# Battery_Guage.net
KiCad netlist of a schematic drawn in Altium Designer
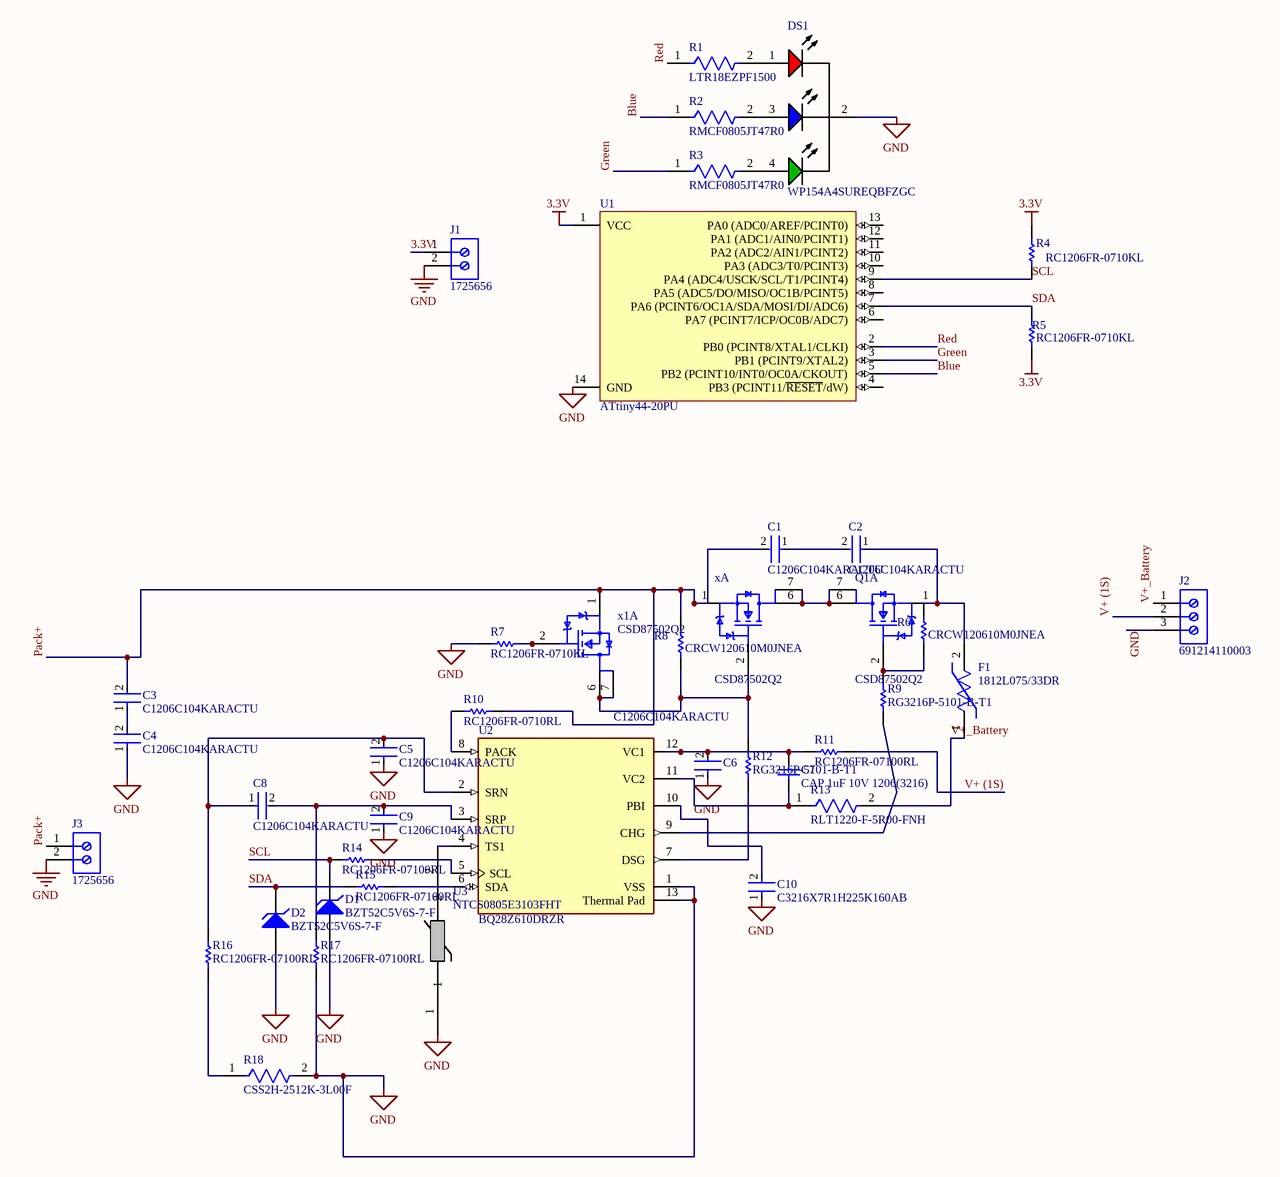
[diagram p0: Battery_Guage.SchDoc]

(export (version "E")
  (design (tool "Eeschema 10.0.6"))
  (components
    (comp (ref "C1")
      (value "C1206C104KARACTU")
      (footprint "FP-C1206C-EB-MFG")
      (description "CAP CER 0.1UF 250V X7R 1206")
      (fields (field (name "MANUFACTURER") "KEMET") (field (name "TOLERANCE") "0.1"))
      (libsource (lib "Altium Content Vault") (part "b4654b650e69147ec39a6b967a45e02"))
    )
    (comp (ref "C2")
      (value "C1206C104KARACTU")
      (footprint "FP-C1206C-EB-MFG")
      (description "CAP CER 0.1UF 250V X7R 1206")
      (fields (field (name "MANUFACTURER") "KEMET") (field (name "TOLERANCE") "0.1"))
      (libsource (lib "Altium Content Vault") (part "b4654b650e69147ec39a6b967a45e02"))
    )
    (comp (ref "C3")
      (value "C1206C104KARACTU")
      (footprint "FP-C1206C-EB-MFG")
      (description "CAP CER 0.1UF 250V X7R 1206")
      (fields (field (name "MANUFACTURER") "KEMET") (field (name "TOLERANCE") "0.1"))
      (libsource (lib "Altium Content Vault") (part "b4654b650e69147ec39a6b967a45e02"))
    )
    (comp (ref "C4")
      (value "C1206C104KARACTU")
      (footprint "FP-C1206C-EB-MFG")
      (description "CAP CER 0.1UF 250V X7R 1206")
      (fields (field (name "MANUFACTURER") "KEMET") (field (name "TOLERANCE") "0.1"))
      (libsource (lib "Altium Content Vault") (part "b4654b650e69147ec39a6b967a45e02"))
    )
    (comp (ref "C5")
      (value "C1206C104KARACTU")
      (footprint "FP-C1206C-EB-MFG")
      (description "CAP CER 0.1UF 250V X7R 1206")
      (fields (field (name "MANUFACTURER") "KEMET") (field (name "TOLERANCE") "0.1"))
      (libsource (lib "Altium Content Vault") (part "b4654b650e69147ec39a6b967a45e02"))
    )
    (comp (ref "C6")
      (value "C1206C104KARACTU")
      (footprint "FP-C1206C-EB-MFG")
      (description "CAP CER 0.1UF 250V X7R 1206")
      (fields (field (name "MANUFACTURER") "KEMET") (field (name "TOLERANCE") "0.1"))
      (libsource (lib "Altium Content Vault") (part "b4654b650e69147ec39a6b967a45e02"))
    )
    (comp (ref "C7")
      (value "CAP 1uF 10V 1206(3216)")
      (footprint "CAPC1206(3216)130_L")
      (description "CAP 1uF 10V ±20% 1206 (3216 Metric) Thickness 1.3mm SMD")
      (fields (field (name "TOLERANCE") "Â±20%"))
      (libsource (lib "Altium Content Vault") (part "CAP"))
    )
    (comp (ref "C8")
      (value "C1206C104KARACTU")
      (footprint "FP-C1206C-EB-MFG")
      (description "CAP CER 0.1UF 250V X7R 1206")
      (fields (field (name "MANUFACTURER") "KEMET") (field (name "TOLERANCE") "0.1"))
      (libsource (lib "Altium Content Vault") (part "b4654b650e69147ec39a6b967a45e02"))
    )
    (comp (ref "C9")
      (value "C1206C104KARACTU")
      (footprint "FP-C1206C-EB-MFG")
      (description "CAP CER 0.1UF 250V X7R 1206")
      (fields (field (name "MANUFACTURER") "KEMET") (field (name "TOLERANCE") "0.1"))
      (libsource (lib "Altium Content Vault") (part "b4654b650e69147ec39a6b967a45e02"))
    )
    (comp (ref "C10")
      (value "C3216X7R1H225K160AB")
      (footprint "FP-C3216-160-0_2-IPC_A")
      (description "Multilayer Ceramic Capacitors 2.2uF ±10% 50V X7R SMD 1206")
      (fields (field (name "TOLERANCE") "10%"))
      (libsource (lib "Altium Content Vault") (part "11868f565c42a9108669ba33697ecf6"))
    )
    (comp (ref "D1")
      (value "BZT52C5V6S-7-F")
      (footprint "DIOD-SOD323-2_V")
      (description "Surface Mount Zener Diode, 5.6 V, -65 to 150 degC, 2-Pin SOD323, RoHS, Tape and Reel")
      (fields (field (name "MANUFACTURER") "DiodesIncorporated"))
      (libsource (lib "Altium Content Vault") (part "DZEN-AK-2"))
    )
    (comp (ref "D2")
      (value "BZT52C5V6S-7-F")
      (footprint "DIOD-SOD323-2_V")
      (description "Surface Mount Zener Diode, 5.6 V, -65 to 150 degC, 2-Pin SOD323, RoHS, Tape and Reel")
      (fields (field (name "MANUFACTURER") "DiodesIncorporated"))
      (libsource (lib "Altium Content Vault") (part "DZEN-AK-2"))
    )
    (comp (ref "DS1")
      (value "WP154A4SUREQBFZGC")
      (footprint "KING-WP154A4SUREQBFZGC_V")
      (description "Full Color LED Lamp, Dominant Wavelength RGB 630 / 525 / 465 nm, -40 to 85 degC, 4-Pin THD, RoHS")
      (fields (field (name "MANUFACTURER") "Kingbright"))
      (libsource (lib "Altium Content Vault") (part "LED-RGB-AKAA-4"))
    )
    (comp (ref "F1")
      (value "1812L075/33DR")
      (footprint "FP-1812L075-33DR-MFG")
      (description "PTC RESET FUSE 33V 750MA 1812")
      (libsource (lib "Altium Content Vault") (part "fdf083d5f6389a9a1c4e51137f46658"))
    )
    (comp (ref "J1")
      (value "1725656")
      (footprint "PHOE-1725656-2")
      (description "Male Header, Pitch 2.54 mm, 1 x 2 Position, Height 9 mm, Tail Length 3.5 mm")
      (fields (field (name "MANUFACTURER") "Phoenix Contact"))
      (libsource (lib "Altium Content Vault") (part "CN-1P-F-TB2"))
    )
    (comp (ref "J2")
      (value "691214110003")
      (footprint "691214110003")
      (fields (field (name "VOLTAGE") "300V"))
      (libsource (lib "Altium Content Vault") (part "TBL - 1R - 03P - Screw"))
    )
    (comp (ref "J3")
      (value "1725656")
      (footprint "PHOE-1725656-2")
      (description "Male Header, Pitch 2.54 mm, 1 x 2 Position, Height 9 mm, Tail Length 3.5 mm")
      (fields (field (name "MANUFACTURER") "Phoenix Contact"))
      (libsource (lib "Altium Content Vault") (part "CN-1P-F-TB2"))
    )
    (comp (ref "Q1")
      (value "CSD87502Q2")
      (footprint "FP-DQK0006B-MFG")
      (description "MOSFET 2N-CH 30V 5A 6WSON")
      (libsource (lib "Altium Content Vault") (part "fd3cbd9991b3bb74591be4f9c2484a9"))
    )
    (comp (ref "R1")
      (value "LTR18EZPF1500")
      (footprint "FP-LTR18-IPC_A")
      (description "High power chip resistors wide terminal type 150Ω 1% 0.75W 0612")
      (fields (field (name "TOLERANCE") "1%"))
      (libsource (lib "Altium Content Vault") (part "1029c3af85768c4190bb7ad29bc67b5"))
    )
    (comp (ref "R2")
      (value "RMCF0805JT47R0")
      (footprint "FP-RMCF0805-MFG")
      (description "47Ω ±5% 0.125W 0805 Thick Film Chip Resistor AEC-Q200 compliant")
      (fields (field (name "TOLERANCE") "5%"))
      (libsource (lib "Altium Content Vault") (part "1029c3af85768c4190bb7ad29bc67b5"))
    )
    (comp (ref "R3")
      (value "RMCF0805JT47R0")
      (footprint "FP-RMCF0805-MFG")
      (description "47Ω ±5% 0.125W 0805 Thick Film Chip Resistor AEC-Q200 compliant")
      (fields (field (name "TOLERANCE") "5%"))
      (libsource (lib "Altium Content Vault") (part "1029c3af85768c4190bb7ad29bc67b5"))
    )
    (comp (ref "R4")
      (value "RC1206FR-0710KL")
      (footprint "RESC3116X65X40ML10T20")
      (description "Chip Resistor, 10 KOhm, +/- 1%, 0.25 W, -55 to 155 degC, 1206 (3216 Metric), RoHS, Tape and Reel")
      (fields (field (name "TOLERANCE") "1%") (field (name "MANUFACTURER") "Yageo"))
      (libsource (lib "Altium Content Vault") (part "RES-2"))
    )
    (comp (ref "R5")
      (value "RC1206FR-0710KL")
      (footprint "RESC3116X65X40ML10T20")
      (description "Chip Resistor, 10 KOhm, +/- 1%, 0.25 W, -55 to 155 degC, 1206 (3216 Metric), RoHS, Tape and Reel")
      (fields (field (name "TOLERANCE") "1%") (field (name "MANUFACTURER") "Yageo"))
      (libsource (lib "Altium Content Vault") (part "RES-2"))
    )
    (comp (ref "R6")
      (value "CRCW120610M0JNEA")
      (footprint "RESC3216X60X45LL10T20")
      (fields (field (name "MANUFACTURER") "Vishay Dale"))
      (libsource (lib "Altium Content Vault") (part "RES"))
    )
    (comp (ref "R7")
      (value "RC1206FR-0710KL")
      (footprint "RESC3116X65X40ML10T20")
      (description "Chip Resistor, 10 KOhm, +/- 1%, 0.25 W, -55 to 155 degC, 1206 (3216 Metric), RoHS, Tape and Reel")
      (fields (field (name "TOLERANCE") "1%") (field (name "MANUFACTURER") "Yageo"))
      (libsource (lib "Altium Content Vault") (part "RES-2"))
    )
    (comp (ref "R8")
      (value "CRCW120610M0JNEA")
      (footprint "RESC3216X60X45LL10T20")
      (fields (field (name "MANUFACTURER") "Vishay Dale"))
      (libsource (lib "Altium Content Vault") (part "RES"))
    )
    (comp (ref "R9")
      (value "RG3216P-5101-B-T1")
      (footprint "RESC3216X50X50NL20T25")
      (fields (field (name "MANUFACTURER") "Susumu"))
      (libsource (lib "Altium Content Vault") (part "RES"))
    )
    (comp (ref "R10")
      (value "RC1206FR-0710RL")
      (footprint "RESC3116X65X40ML10T20")
      (description "Chip Resistor, 10 Ohm, +/- 1%, 0.25 W, -55 to 155 degC, 1206 (3216 Metric), RoHS, Tape and Reel")
      (fields (field (name "MANUFACTURER") "Yageo") (field (name "TOLERANCE") "1%"))
      (libsource (lib "Altium Content Vault") (part "RES-2"))
    )
    (comp (ref "R11")
      (value "RC1206FR-07100RL")
      (footprint "RESC3116X65X40ML10T20")
      (description "Chip Resistor, 100 Ohm, +/- 1%, 0.25 W, -55 to 155 degC, 1206 (3216 Metric), RoHS, Tape and Reel")
      (fields (field (name "MANUFACTURER") "Yageo") (field (name "TOLERANCE") "1%"))
      (libsource (lib "Altium Content Vault") (part "RES-2"))
    )
    (comp (ref "R12")
      (value "RG3216P-5101-B-T1")
      (footprint "RESC3216X50X50NL20T25")
      (fields (field (name "MANUFACTURER") "Susumu"))
      (libsource (lib "Altium Content Vault") (part "RES"))
    )
    (comp (ref "R13")
      (value "RLT1220-F-5R00-FNH")
      (footprint "FP-RLT1220-F-MFG")
      (description "RES SMD 5 OHM 1% 1/3W 0805")
      (libsource (lib "Altium Content Vault") (part "1029c3af85768c4190bb7ad29bc67b5"))
    )
    (comp (ref "R14")
      (value "RC1206FR-07100RL")
      (footprint "RESC3116X65X40ML10T20")
      (description "Chip Resistor, 100 Ohm, +/- 1%, 0.25 W, -55 to 155 degC, 1206 (3216 Metric), RoHS, Tape and Reel")
      (fields (field (name "MANUFACTURER") "Yageo") (field (name "TOLERANCE") "1%"))
      (libsource (lib "Altium Content Vault") (part "RES-2"))
    )
    (comp (ref "R15")
      (value "RC1206FR-07100RL")
      (footprint "RESC3116X65X40ML10T20")
      (description "Chip Resistor, 100 Ohm, +/- 1%, 0.25 W, -55 to 155 degC, 1206 (3216 Metric), RoHS, Tape and Reel")
      (fields (field (name "MANUFACTURER") "Yageo") (field (name "TOLERANCE") "1%"))
      (libsource (lib "Altium Content Vault") (part "RES-2"))
    )
    (comp (ref "R16")
      (value "RC1206FR-07100RL")
      (footprint "RESC3116X65X40ML10T20")
      (description "Chip Resistor, 100 Ohm, +/- 1%, 0.25 W, -55 to 155 degC, 1206 (3216 Metric), RoHS, Tape and Reel")
      (fields (field (name "MANUFACTURER") "Yageo") (field (name "TOLERANCE") "1%"))
      (libsource (lib "Altium Content Vault") (part "RES-2"))
    )
    (comp (ref "R17")
      (value "RC1206FR-07100RL")
      (footprint "RESC3116X65X40ML10T20")
      (description "Chip Resistor, 100 Ohm, +/- 1%, 0.25 W, -55 to 155 degC, 1206 (3216 Metric), RoHS, Tape and Reel")
      (fields (field (name "MANUFACTURER") "Yageo") (field (name "TOLERANCE") "1%"))
      (libsource (lib "Altium Content Vault") (part "RES-2"))
    )
    (comp (ref "R18")
      (value "CSS2H-2512K-3L00F")
      (footprint "FP-CSS2H-2512K-3L00F-MFG")
      (description "CSS2H-2512K-3L00F Res Metal Strip 2512 0.003 Ohm 1% 4W ±75ppm/C Pad SMD Automotive T/R")
      (fields (field (name "TOLERANCE") "1%"))
      (libsource (lib "Altium Content Vault") (part "1029c3af85768c4190bb7ad29bc67b5"))
    )
    (comp (ref "U1")
      (value "ATtiny44-20PU")
      (footprint "14P3")
      (libsource (lib "Altium Content Vault") (part "MC-8B-ATTINY24V-IL14"))
    )
    (comp (ref "U2")
      (value "BQ28Z610DRZR")
      (footprint "FP-DRZ0012A-MFG")
      (description "IC BATT GAS GAUGE LIION 12SON")
      (libsource (lib "Altium Content Vault") (part "45a40ba0b7cf2a0dd5636c134825ee4"))
    )
    (comp (ref "U3")
      (value "NTCS0805E3103FHT")
      (footprint "NTCS0805_VIS")
      (description "THERMISTOR NTC 10KOHM 3940K 0805")
      (fields (field (name "TOLERANCE") "1%"))
      (libsource (lib "Altium Content Vault") (part "NTCS0805E3103FHT"))
    )
    (comp (ref "x")
      (value "CSD87502Q2")
      (footprint "FP-DQK0006B-MFG")
      (description "MOSFET 2N-CH 30V 5A 6WSON")
      (libsource (lib "Altium Content Vault") (part "fd3cbd9991b3bb74591be4f9c2484a9"))
    )
    (comp (ref "x1")
      (value "CSD87502Q2")
      (footprint "FP-DQK0006B-MFG")
      (description "MOSFET 2N-CH 30V 5A 6WSON")
      (libsource (lib "Altium Content Vault") (part "fd3cbd9991b3bb74591be4f9c2484a9"))
    )
  )
  (nets
    (net (code "1") (name "/Blue") (class "Default")
      (node (ref "R2") (pin "1") (pinfunction "1_1") (pintype "passive"))
      (node (ref "U1") (pin "5") (pinfunction "PB2_(PCINT10/INT0/OC0A/CKOUT)_5") (pintype "bidirectional"))
    )
    (net (code "2") (name "/Green") (class "Default")
      (node (ref "R3") (pin "1") (pinfunction "1_1") (pintype "passive"))
      (node (ref "U1") (pin "3") (pinfunction "PB1_(PCINT9/XTAL2)_3") (pintype "bidirectional"))
    )
    (net (code "3") (name "/Pack+") (class "Default")
      (node (ref "C1") (pin "2") (pinfunction "2_2") (pintype "passive"))
      (node (ref "C3") (pin "2") (pinfunction "2_2") (pintype "passive"))
      (node (ref "J3") (pin "1") (pinfunction "1_1") (pintype "passive"))
      (node (ref "R10") (pin "2") (pinfunction "2_2") (pintype "passive"))
      (node (ref "R8") (pin "2") (pinfunction "2_2") (pintype "passive"))
      (node (ref "x") (pin "1") (pinfunction "S1_1") (pintype "passive"))
      (node (ref "x1") (pin "1") (pinfunction "S1_1") (pintype "passive"))
    )
    (net (code "4") (name "/Red") (class "Default")
      (node (ref "R1") (pin "1") (pinfunction "1_1") (pintype "passive"))
      (node (ref "U1") (pin "2") (pinfunction "PB0_(PCINT8/XTAL1/CLKI)_2") (pintype "bidirectional"))
    )
    (net (code "5") (name "/SCL") (class "Default")
      (node (ref "D1") (pin "2") (pinfunction "K_2") (pintype "passive"))
      (node (ref "R14") (pin "1") (pinfunction "1_1") (pintype "passive"))
      (node (ref "R4") (pin "1") (pinfunction "1_1") (pintype "passive"))
      (node (ref "U1") (pin "9") (pinfunction "PA4_(ADC4/USCK/SCL/T1/PCINT4)_9") (pintype "bidirectional"))
    )
    (net (code "6") (name "/SDA") (class "Default")
      (node (ref "D2") (pin "2") (pinfunction "K_2") (pintype "passive"))
      (node (ref "R15") (pin "1") (pinfunction "1_1") (pintype "passive"))
      (node (ref "R5") (pin "2") (pinfunction "2_2") (pintype "passive"))
      (node (ref "U1") (pin "7") (pinfunction "PA6_(PCINT6/OC1A/SDA/MOSI/DI/ADC6)_7") (pintype "bidirectional"))
    )
    (net (code "7") (name "/V+ (1S)") (class "Default")
      (node (ref "J2") (pin "2") (pinfunction "2_2") (pintype "passive"))
      (node (ref "R11") (pin "1") (pinfunction "1_1") (pintype "passive"))
    )
    (net (code "8") (name "/V+_Battery") (class "Default")
      (node (ref "F1") (pin "1") (pinfunction "1_1") (pintype "passive"))
      (node (ref "J2") (pin "1") (pinfunction "1_1") (pintype "passive"))
      (node (ref "R13") (pin "2") (pinfunction "2_2") (pintype "passive"))
    )
    (net (code "9") (name "3.3V") (class "Default")
      (node (ref "J1") (pin "1") (pinfunction "1_1") (pintype "passive"))
      (node (ref "R4") (pin "2") (pinfunction "2_2") (pintype "passive"))
      (node (ref "R5") (pin "1") (pinfunction "1_1") (pintype "passive"))
      (node (ref "U1") (pin "1") (pinfunction "VCC_1") (pintype "power_in"))
    )
    (net (code "10") (name "GND") (class "Default")
      (node (ref "C10") (pin "1") (pinfunction "1_1") (pintype "passive"))
      (node (ref "C4") (pin "1") (pinfunction "1_1") (pintype "passive"))
      (node (ref "C5") (pin "1") (pinfunction "1_1") (pintype "passive"))
      (node (ref "C6") (pin "1") (pinfunction "1_1") (pintype "passive"))
      (node (ref "C9") (pin "1") (pinfunction "1_1") (pintype "passive"))
      (node (ref "D1") (pin "1") (pinfunction "A_1") (pintype "passive"))
      (node (ref "D2") (pin "1") (pinfunction "A_1") (pintype "passive"))
      (node (ref "DS1") (pin "2") (pinfunction "CATHODE_2") (pintype "passive"))
      (node (ref "J1") (pin "2") (pinfunction "2_2") (pintype "passive"))
      (node (ref "J2") (pin "3") (pinfunction "3_3") (pintype "passive"))
      (node (ref "J3") (pin "2") (pinfunction "2_2") (pintype "passive"))
      (node (ref "R17") (pin "1") (pinfunction "1_1") (pintype "passive"))
      (node (ref "R18") (pin "2") (pinfunction "2_2") (pintype "passive"))
      (node (ref "R7") (pin "1") (pinfunction "1_1") (pintype "passive"))
      (node (ref "U1") (pin "14") (pinfunction "GND_14") (pintype "power_in"))
      (node (ref "U2") (pin "1") (pinfunction "VSS_1") (pintype "power_in"))
      (node (ref "U2") (pin "13") (pinfunction "Thermal_Pad_13") (pintype "power_in"))
      (node (ref "U3") (pin "1") (pinfunction "1_1") (pintype "passive"))
    )
    (net (code "11") (name "Net-(C1-Pad1)") (class "Default")
      (node (ref "C1") (pin "1") (pinfunction "1_1") (pintype "passive"))
      (node (ref "C2") (pin "2") (pinfunction "2_2") (pintype "passive"))
    )
    (net (code "12") (name "Net-(C3-Pad1)") (class "Default")
      (node (ref "C3") (pin "1") (pinfunction "1_1") (pintype "passive"))
      (node (ref "C4") (pin "2") (pinfunction "2_2") (pintype "passive"))
    )
    (net (code "13") (name "Net-(DS1-BLUE)") (class "Default")
      (node (ref "DS1") (pin "3") (pinfunction "BLUE_3") (pintype "passive"))
      (node (ref "R2") (pin "2") (pinfunction "2_2") (pintype "passive"))
    )
    (net (code "14") (name "Net-(DS1-GREEN)") (class "Default")
      (node (ref "DS1") (pin "4") (pinfunction "GREEN_4") (pintype "passive"))
      (node (ref "R3") (pin "2") (pinfunction "2_2") (pintype "passive"))
    )
    (net (code "15") (name "Net-(DS1-RED)") (class "Default")
      (node (ref "DS1") (pin "1") (pinfunction "RED_1") (pintype "passive"))
      (node (ref "R1") (pin "2") (pinfunction "2_2") (pintype "passive"))
    )
    (net (code "16") (name "Net-(Q1A-D1-Pad6)") (class "Default")
      (node (ref "Q1") (pin "6") (pinfunction "D1_6") (pintype "passive"))
      (node (ref "Q1") (pin "7") (pinfunction "D1_7") (pintype "passive"))
      (node (ref "x") (pin "6") (pinfunction "D1_6") (pintype "passive"))
      (node (ref "x") (pin "7") (pinfunction "D1_7") (pintype "passive"))
    )
    (net (code "17") (name "Net-(Q1A-G1)") (class "Default")
      (node (ref "Q1") (pin "2") (pinfunction "G1_2") (pintype "passive"))
      (node (ref "R6") (pin "1") (pinfunction "1_1") (pintype "passive"))
      (node (ref "R9") (pin "2") (pinfunction "2_2") (pintype "passive"))
    )
    (net (code "18") (name "Net-(Q1A-S1)") (class "Default")
      (node (ref "C2") (pin "1") (pinfunction "1_1") (pintype "passive"))
      (node (ref "F1") (pin "2") (pinfunction "2_2") (pintype "passive"))
      (node (ref "Q1") (pin "1") (pinfunction "S1_1") (pintype "passive"))
      (node (ref "R6") (pin "2") (pinfunction "2_2") (pintype "passive"))
    )
    (net (code "19") (name "Net-(R16-Pad1)") (class "Default")
      (node (ref "R16") (pin "1") (pinfunction "1_1") (pintype "passive"))
      (node (ref "R18") (pin "1") (pinfunction "1_1") (pintype "passive"))
    )
    (net (code "20") (name "Net-(U2-CHG)") (class "Default")
      (node (ref "R9") (pin "1") (pinfunction "1_1") (pintype "passive"))
      (node (ref "U2") (pin "9") (pinfunction "CHG_9") (pintype "output"))
    )
    (net (code "21") (name "Net-(U2-DSG)") (class "Default")
      (node (ref "R12") (pin "1") (pinfunction "1_1") (pintype "passive"))
      (node (ref "U2") (pin "7") (pinfunction "DSG_7") (pintype "output"))
    )
    (net (code "22") (name "Net-(U2-PACK)") (class "Default")
      (node (ref "R10") (pin "1") (pinfunction "1_1") (pintype "passive"))
      (node (ref "U2") (pin "8") (pinfunction "PACK_8") (pintype "input"))
    )
    (net (code "23") (name "Net-(U2-PBI)") (class "Default")
      (node (ref "C10") (pin "2") (pinfunction "2_2") (pintype "passive"))
      (node (ref "U2") (pin "10") (pinfunction "PBI_10") (pintype "power_in"))
    )
    (net (code "24") (name "Net-(U2-SCL)") (class "Default")
      (node (ref "R14") (pin "2") (pinfunction "2_2") (pintype "passive"))
      (node (ref "U2") (pin "5") (pinfunction "SCL_5") (pintype "input"))
    )
    (net (code "25") (name "Net-(U2-SDA)") (class "Default")
      (node (ref "R15") (pin "2") (pinfunction "2_2") (pintype "passive"))
      (node (ref "U2") (pin "6") (pinfunction "SDA_6") (pintype "bidirectional"))
    )
    (net (code "26") (name "Net-(U2-SRN)") (class "Default")
      (node (ref "C5") (pin "2") (pinfunction "2_2") (pintype "passive"))
      (node (ref "C8") (pin "1") (pinfunction "1_1") (pintype "passive"))
      (node (ref "R16") (pin "2") (pinfunction "2_2") (pintype "passive"))
      (node (ref "U2") (pin "2") (pinfunction "SRN_2") (pintype "input"))
    )
    (net (code "27") (name "Net-(U2-SRP)") (class "Default")
      (node (ref "C8") (pin "2") (pinfunction "2_2") (pintype "passive"))
      (node (ref "C9") (pin "2") (pinfunction "2_2") (pintype "passive"))
      (node (ref "R17") (pin "2") (pinfunction "2_2") (pintype "passive"))
      (node (ref "U2") (pin "3") (pinfunction "SRP_3") (pintype "input"))
    )
    (net (code "28") (name "Net-(U2-TS1)") (class "Default")
      (node (ref "U2") (pin "4") (pinfunction "TS1_4") (pintype "input"))
      (node (ref "U3") (pin "2") (pinfunction "2_2") (pintype "passive"))
    )
    (net (code "29") (name "Net-(U2-VC1)") (class "Default")
      (node (ref "C6") (pin "2") (pinfunction "2_2") (pintype "passive"))
      (node (ref "C7") (pin "2") (pinfunction "2_2") (pintype "passive"))
      (node (ref "R11") (pin "2") (pinfunction "2_2") (pintype "passive"))
      (node (ref "U2") (pin "12") (pinfunction "VC1_12") (pintype "power_in"))
    )
    (net (code "30") (name "Net-(U2-VC2)") (class "Default")
      (node (ref "C7") (pin "1") (pinfunction "1_1") (pintype "passive"))
      (node (ref "R13") (pin "1") (pinfunction "1_1") (pintype "passive"))
      (node (ref "U2") (pin "11") (pinfunction "VC2_11") (pintype "power_in"))
    )
    (net (code "31") (name "Net-(x1A-G1)") (class "Default")
      (node (ref "R7") (pin "2") (pinfunction "2_2") (pintype "passive"))
      (node (ref "x1") (pin "2") (pinfunction "G1_2") (pintype "passive"))
    )
    (net (code "32") (name "Net-(xA-G1)") (class "Default")
      (node (ref "R12") (pin "2") (pinfunction "2_2") (pintype "passive"))
      (node (ref "R8") (pin "1") (pinfunction "1_1") (pintype "passive"))
      (node (ref "x") (pin "2") (pinfunction "G1_2") (pintype "passive"))
      (node (ref "x1") (pin "6") (pinfunction "D1_6") (pintype "passive"))
      (node (ref "x1") (pin "7") (pinfunction "D1_7") (pintype "passive"))
    )
    (net (code "33") (name "unconnected-(U1-PA0_(ADC0{slash}AREF{slash}PCINT0)-Pad13)") (class "Default")
      (node (ref "U1") (pin "13") (pinfunction "PA0_(ADC0/AREF/PCINT0)_13") (pintype "bidirectional"))
    )
    (net (code "34") (name "unconnected-(U1-PA1_(ADC1{slash}AIN0{slash}PCINT1)-Pad12)") (class "Default")
      (node (ref "U1") (pin "12") (pinfunction "PA1_(ADC1/AIN0/PCINT1)_12") (pintype "bidirectional"))
    )
    (net (code "35") (name "unconnected-(U1-PA2_(ADC2{slash}AIN1{slash}PCINT2)-Pad11)") (class "Default")
      (node (ref "U1") (pin "11") (pinfunction "PA2_(ADC2/AIN1/PCINT2)_11") (pintype "bidirectional"))
    )
    (net (code "36") (name "unconnected-(U1-PA3_(ADC3{slash}T0{slash}PCINT3)-Pad10)") (class "Default")
      (node (ref "U1") (pin "10") (pinfunction "PA3_(ADC3/T0/PCINT3)_10") (pintype "bidirectional"))
    )
    (net (code "37") (name "unconnected-(U1-PA5_(ADC5{slash}DO{slash}MISO{slash}OC1B{slash}PCINT5)-Pad8)") (class "Default")
      (node (ref "U1") (pin "8") (pinfunction "PA5_(ADC5/DO/MISO/OC1B/PCINT5)_8") (pintype "bidirectional"))
    )
    (net (code "38") (name "unconnected-(U1-PA7_(PCINT7{slash}ICP{slash}OC0B{slash}ADC7)-Pad6)") (class "Default")
      (node (ref "U1") (pin "6") (pinfunction "PA7_(PCINT7/ICP/OC0B/ADC7)_6") (pintype "bidirectional"))
    )
    (net (code "39") (name "unconnected-(U1-PB3_(PCINT11{slash}~{RESET}{slash}dW)-Pad4)") (class "Default")
      (node (ref "U1") (pin "4") (pinfunction "PB3_(PCINT11/~{RESET}/dW)_4") (pintype "bidirectional"))
    )
  )
)
